# msp430g2330_dip.net
KiCad netlist of a schematic drawn in EAGLE
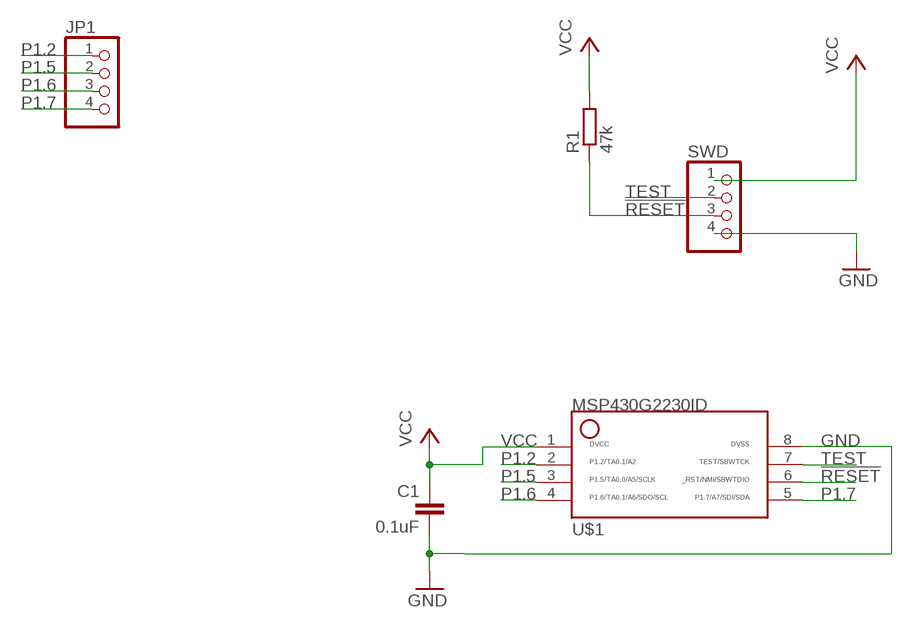
[diagram p0: schematic, sheet 1]

(export (version "E")
  (design (tool "Eeschema 10.0.6"))
  (components
    (comp (ref "C1")
      (value "0.1uF")
      (footprint "eagle-import:C0805")
      (libsource (lib "eagle-import") (part "C-EUC0805"))
    )
    (comp (ref "JP1")
      (value "PINHD-1X4")
      (footprint "eagle-import:1X04")
      (libsource (lib "eagle-import") (part "PINHD-1X4"))
    )
    (comp (ref "R1")
      (value "47k")
      (footprint "eagle-import:R0805")
      (libsource (lib "eagle-import") (part "R-EU_R0805"))
    )
    (comp (ref "SWD")
      (value "PINHD-1X4")
      (footprint "eagle-import:1X04")
      (libsource (lib "eagle-import") (part "PINHD-1X4"))
    )
    (comp (ref "U$1")
      (value "MSP430G2230ID")
      (footprint "eagle-import:SO08")
      (libsource (lib "eagle-import") (part "MSP430G2230ID"))
    )
  )
  (nets
    (net (code "1") (name "/P1.2") (class "Default")
      (node (ref "JP1") (pin "1") (pinfunction "1_1") (pintype "passive"))
      (node (ref "U$1") (pin "2") (pinfunction "2_2") (pintype "bidirectional"))
    )
    (net (code "2") (name "/P1.5") (class "Default")
      (node (ref "JP1") (pin "2") (pinfunction "2_2") (pintype "passive"))
      (node (ref "U$1") (pin "3") (pinfunction "3_3") (pintype "bidirectional"))
    )
    (net (code "3") (name "/P1.6") (class "Default")
      (node (ref "JP1") (pin "3") (pinfunction "3_3") (pintype "passive"))
      (node (ref "U$1") (pin "4") (pinfunction "4_4") (pintype "bidirectional"))
    )
    (net (code "4") (name "/P1.7") (class "Default")
      (node (ref "JP1") (pin "4") (pinfunction "4_4") (pintype "passive"))
      (node (ref "U$1") (pin "5") (pinfunction "5_5") (pintype "bidirectional"))
    )
    (net (code "5") (name "/TEST") (class "Default")
      (node (ref "SWD") (pin "2") (pinfunction "2_2") (pintype "passive"))
      (node (ref "U$1") (pin "7") (pinfunction "7_7") (pintype "bidirectional"))
    )
    (net (code "6") (name "/~{RESET}") (class "Default")
      (node (ref "R1") (pin "1") (pinfunction "1_1") (pintype "passive"))
      (node (ref "SWD") (pin "3") (pinfunction "3_3") (pintype "passive"))
      (node (ref "U$1") (pin "6") (pinfunction "6_6") (pintype "bidirectional"))
    )
    (net (code "7") (name "GND") (class "Default")
      (node (ref "C1") (pin "2") (pinfunction "2_2") (pintype "passive"))
      (node (ref "SWD") (pin "4") (pinfunction "4_4") (pintype "passive"))
      (node (ref "U$1") (pin "8") (pinfunction "8_8") (pintype "power_in"))
    )
    (net (code "8") (name "VCC") (class "Default")
      (node (ref "C1") (pin "1") (pinfunction "1_1") (pintype "passive"))
      (node (ref "R1") (pin "2") (pinfunction "2_2") (pintype "passive"))
      (node (ref "SWD") (pin "1") (pinfunction "1_1") (pintype "passive"))
      (node (ref "U$1") (pin "1") (pinfunction "1_1") (pintype "power_in"))
    )
  )
)
